# Sheet3.net
KiCad netlist of a schematic drawn in Altium Designer
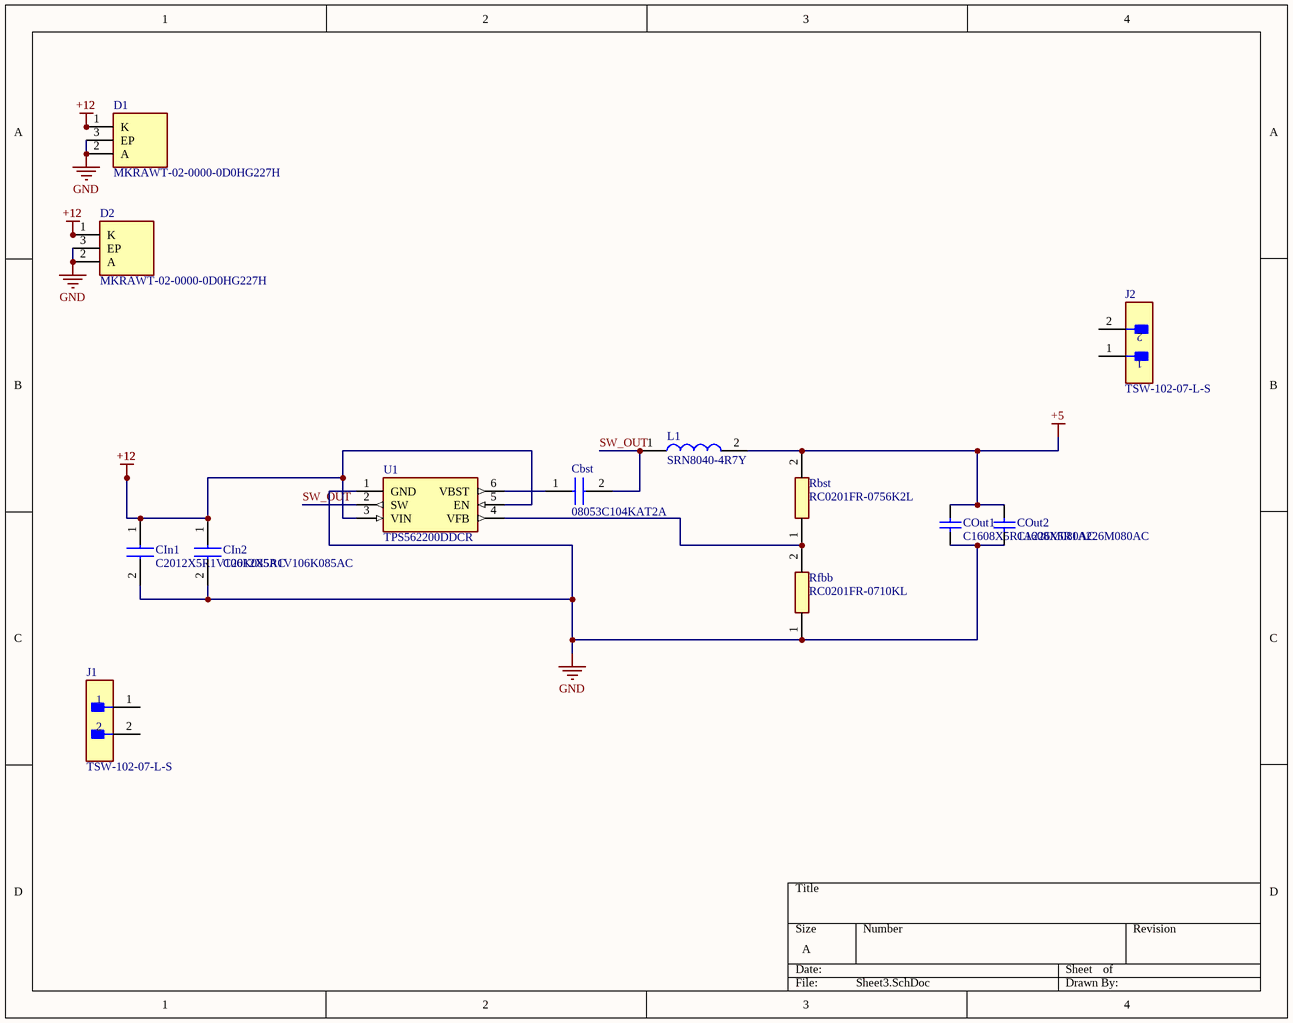
[diagram p0: Sheet3.SchDoc]

(export (version "E")
  (design (tool "Eeschema 10.0.6"))
  (components
    (comp (ref "Cbst")
      (value "08053C104KAT2A")
      (footprint "SamacSys:CAPC2012X94N")
      (description "Capacitor")
      (fields (field (name "MOUSER PART NUMBER") "581-08053C104K"))
      (libsource (lib "*") (part "08053C104KAT2A"))
    )
    (comp (ref "CIn1")
      (value "C2012X5R1V106K085AC")
      (footprint "SamacSys:C2012_Commercial")
      (description "Capacitor")
      (fields (field (name "MOUSER PART NUMBER") "810-C2012X5R1V106K0C"))
      (libsource (lib "*") (part "C2012X5R1V106K085AC"))
    )
    (comp (ref "CIn2")
      (value "C2012X5R1V106K085AC")
      (footprint "SamacSys:C2012_Commercial")
      (description "Capacitor")
      (fields (field (name "MOUSER PART NUMBER") "810-C2012X5R1V106K0C"))
      (libsource (lib "*") (part "C2012X5R1V106K085AC"))
    )
    (comp (ref "COut1")
      (value "C1608X5R1A226M080AC")
      (footprint "CAPC1608X100X20ML10")
      (description "Chip Capacitor, 22 uF, +/- 20%, 10 V, -55 to 85 degC, 0603 (1608 Metric), RoHS, Tape and Reel")
      (fields (field (name "MANUFACTURER") "TDK") (field (name "TOLERANCE") "±20%"))
      (libsource (lib "Altium Content Vault") (part "CAP-NP-2"))
    )
    (comp (ref "COut2")
      (value "C1608X5R1A226M080AC")
      (footprint "CAPC1608X100X20ML10")
      (description "Chip Capacitor, 22 uF, +/- 20%, 10 V, -55 to 85 degC, 0603 (1608 Metric), RoHS, Tape and Reel")
      (fields (field (name "MANUFACTURER") "TDK") (field (name "TOLERANCE") "±20%"))
      (libsource (lib "Altium Content Vault") (part "CAP-NP-2"))
    )
    (comp (ref "D1")
      (value "MKRAWT-02-0000-0D0HG227H")
      (footprint "SamacSys:MKRAWT0200000D0HG227H")
      (description "LED")
      (fields (field (name "MOUSER PART NUMBER") "941-MKRAWT20D0HG227H"))
      (libsource (lib "*") (part "MKRAWT-02-0000-0D0HG227H"))
    )
    (comp (ref "D2")
      (value "MKRAWT-02-0000-0D0HG227H")
      (footprint "SamacSys:MKRAWT0200000D0HG227H")
      (description "LED")
      (fields (field (name "MOUSER PART NUMBER") "941-MKRAWT20D0HG227H"))
      (libsource (lib "*") (part "MKRAWT-02-0000-0D0HG227H"))
    )
    (comp (ref "J1")
      (value "TSW-102-07-L-S")
      (footprint "FP-TSW-102-07-L-S-MFG")
      (description "CONN HEADER VERT 2POS 2.54MM")
      (libsource (lib "Altium Content Vault") (part "3bc925449376181038e59eaffc5286c"))
    )
    (comp (ref "J2")
      (value "TSW-102-07-L-S")
      (footprint "FP-TSW-102-07-L-S-MFG")
      (description "CONN HEADER VERT 2POS 2.54MM")
      (libsource (lib "") (part "3bc925449376181038e59eaffc5286c_1"))
    )
    (comp (ref "L1")
      (value "SRN8040-4R7Y")
      (footprint "SamacSys:SRN80404R7Y")
      (description "Inductor")
      (fields (field (name "MOUSER PART NUMBER") "652-SRN8040-4R7Y"))
      (libsource (lib "*") (part "SRN8040-4R7Y"))
    )
    (comp (ref "Rbst")
      (value "RC0201FR-0756K2L")
      (footprint "SamacSys:RESC0603X26N")
      (description "Resistor")
      (fields (field (name "MOUSER PART NUMBER") "603-RC0201FR-0756K2L"))
      (libsource (lib "*") (part "RC0201FR-0756K2L"))
    )
    (comp (ref "Rfbb")
      (value "RC0201FR-0710KL")
      (footprint "SamacSys:RESC0603X26N")
      (description "Resistor")
      (fields (field (name "MOUSER PART NUMBER") "603-RC0201FR-0710KL"))
      (libsource (lib "*") (part "RC0201FR-0710KL"))
    )
    (comp (ref "U1")
      (value "TPS562200DDCR")
      (footprint "SamacSys:SOT95P280X110-6N")
      (description "Undefined or Miscellaneous")
      (fields (field (name "MOUSER PART NUMBER") "595-TPS562200DDCR"))
      (libsource (lib "*") (part "TPS562200DDCR"))
    )
  )
  (nets
    (net (code "1") (name "+5") (class "Default")
      (node (ref "COut1") (pin "2") (pinfunction "2_2") (pintype "passive"))
      (node (ref "COut2") (pin "2") (pinfunction "2_2") (pintype "passive"))
      (node (ref "L1") (pin "2") (pinfunction "2_2") (pintype "passive"))
      (node (ref "Rbst") (pin "2") (pinfunction "2_2") (pintype "passive"))
    )
    (net (code "2") (name "+12") (class "Default")
      (node (ref "CIn1") (pin "1") (pinfunction "1_1") (pintype "passive"))
      (node (ref "CIn2") (pin "1") (pinfunction "1_1") (pintype "passive"))
      (node (ref "D1") (pin "1") (pinfunction "K_1") (pintype "passive"))
      (node (ref "D2") (pin "1") (pinfunction "K_1") (pintype "passive"))
      (node (ref "U1") (pin "3") (pinfunction "VIN_3") (pintype "input"))
      (node (ref "U1") (pin "5") (pinfunction "EN_5") (pintype "input"))
    )
    (net (code "3") (name "/SW_OUT") (class "Default")
      (node (ref "Cbst") (pin "2") (pinfunction "2_2") (pintype "passive"))
      (node (ref "L1") (pin "1") (pinfunction "1_1") (pintype "passive"))
      (node (ref "U1") (pin "2") (pinfunction "SW_2") (pintype "output"))
    )
    (net (code "4") (name "GND") (class "Default")
      (node (ref "CIn1") (pin "2") (pinfunction "2_2") (pintype "passive"))
      (node (ref "CIn2") (pin "2") (pinfunction "2_2") (pintype "passive"))
      (node (ref "COut1") (pin "1") (pinfunction "1_1") (pintype "passive"))
      (node (ref "COut2") (pin "1") (pinfunction "1_1") (pintype "passive"))
      (node (ref "D1") (pin "2") (pinfunction "A_2") (pintype "passive"))
      (node (ref "D1") (pin "3") (pinfunction "EP_3") (pintype "passive"))
      (node (ref "D2") (pin "2") (pinfunction "A_2") (pintype "passive"))
      (node (ref "D2") (pin "3") (pinfunction "EP_3") (pintype "passive"))
      (node (ref "Rfbb") (pin "1") (pinfunction "1_1") (pintype "passive"))
      (node (ref "U1") (pin "1") (pinfunction "GND_1") (pintype "power_in"))
    )
    (net (code "5") (name "Net-(U1-VBST)") (class "Default")
      (node (ref "Cbst") (pin "1") (pinfunction "1_1") (pintype "passive"))
      (node (ref "U1") (pin "6") (pinfunction "VBST_6") (pintype "output"))
    )
    (net (code "6") (name "Net-(U1-VFB)") (class "Default")
      (node (ref "Rbst") (pin "1") (pinfunction "1_1") (pintype "passive"))
      (node (ref "Rfbb") (pin "2") (pinfunction "2_2") (pintype "passive"))
      (node (ref "U1") (pin "4") (pinfunction "VFB_4") (pintype "output"))
    )
    (net (code "7") (name "unconnected-(J1-Pad1)") (class "Default")
      (node (ref "J1") (pin "1") (pinfunction "1_1") (pintype "passive"))
    )
    (net (code "8") (name "unconnected-(J1-Pad2)") (class "Default")
      (node (ref "J1") (pin "2") (pinfunction "2_2") (pintype "passive"))
    )
    (net (code "9") (name "unconnected-(J2-Pad1)") (class "Default")
      (node (ref "J2") (pin "1") (pinfunction "1_1") (pintype "passive"))
    )
    (net (code "10") (name "unconnected-(J2-Pad2)") (class "Default")
      (node (ref "J2") (pin "2") (pinfunction "2_2") (pintype "passive"))
    )
  )
)
